# arduino_v2.net
KiCad netlist of a schematic drawn in EAGLE
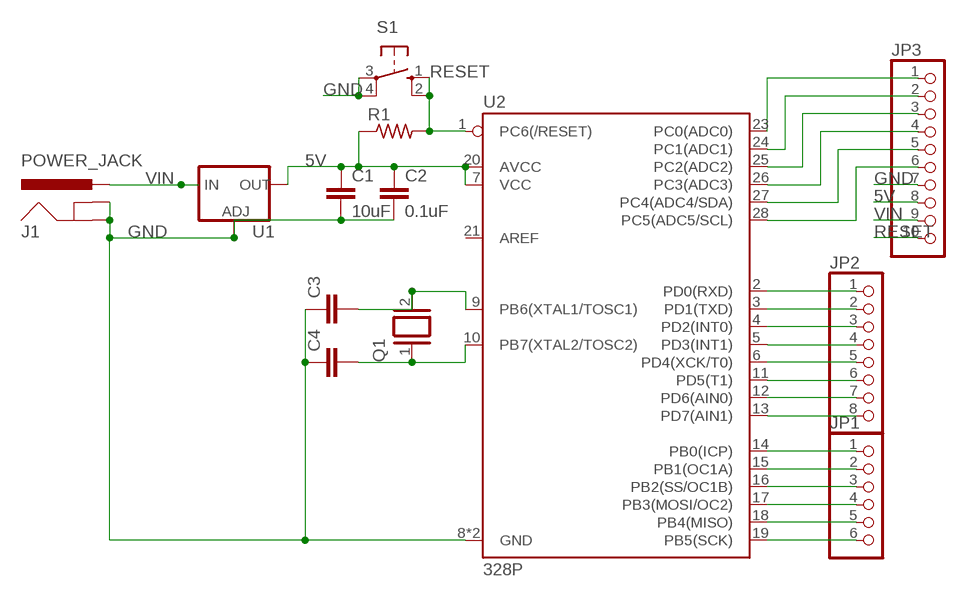
[diagram p0: schematic, sheet 1]

(export (version "E")
  (design (tool "Eeschema 10.0.6"))
  (components
    (comp (ref "C1")
      (value "10uF")
      (footprint "eagle-import:C025-024X044")
      (libsource (lib "eagle-import") (part "C-EU025-024X044"))
    )
    (comp (ref "C2")
      (value "0.1uF")
      (footprint "eagle-import:C025-024X044")
      (libsource (lib "eagle-import") (part "C-EU025-024X044"))
    )
    (comp (ref "C3")
      (value "C-EU025-024X044")
      (footprint "eagle-import:C025-024X044")
      (libsource (lib "eagle-import") (part "C-EU025-024X044"))
    )
    (comp (ref "C4")
      (value "C-EU025-024X044")
      (footprint "eagle-import:C025-024X044")
      (libsource (lib "eagle-import") (part "C-EU025-024X044"))
    )
    (comp (ref "J1")
      (value "POWER_JACK")
      (footprint "eagle-import:POWER_JACK_PTH")
      (libsource (lib "eagle-import") (part "POWER_JACK"))
    )
    (comp (ref "JP1")
      (value "PINHD-1X6")
      (footprint "eagle-import:1X06")
      (libsource (lib "eagle-import") (part "PINHD-1X6"))
    )
    (comp (ref "JP2")
      (value "PINHD-1X8")
      (footprint "eagle-import:1X08")
      (libsource (lib "eagle-import") (part "PINHD-1X8"))
    )
    (comp (ref "JP3")
      (value "PINHD-1X10")
      (footprint "eagle-import:1X10")
      (libsource (lib "eagle-import") (part "PINHD-1X10"))
    )
    (comp (ref "Q1")
      (value "XTAL/S")
      (footprint "eagle-import:QS")
      (libsource (lib "eagle-import") (part "XTAL/S"))
    )
    (comp (ref "R1")
      (value "R-US_0204/7")
      (footprint "eagle-import:0204_7")
      (libsource (lib "eagle-import") (part "R-US_0204/7"))
    )
    (comp (ref "S1")
      (value "10-XX")
      (footprint "eagle-import:B3F-10XX")
      (fields (field (name "MPN") "B3F-1000"))
      (libsource (lib "eagle-import") (part "10-XX"))
    )
    (comp (ref "U1")
      (value "V_REG_LM1117SOT223")
      (footprint "eagle-import:SOT223")
      (libsource (lib "eagle-import") (part "V_REG_LM1117SOT223"))
    )
    (comp (ref "U2")
      (value "328P")
      (footprint "eagle-import:DIP28")
      (libsource (lib "eagle-import") (part "ATMEGA328P_PDIP"))
    )
  )
  (nets
    (net (code "1") (name "/5V") (class "Default")
      (node (ref "C1") (pin "1") (pinfunction "1_1") (pintype "passive"))
      (node (ref "C2") (pin "1") (pinfunction "1_1") (pintype "passive"))
      (node (ref "JP3") (pin "8") (pinfunction "8_8") (pintype "passive"))
      (node (ref "R1") (pin "1") (pinfunction "1_1") (pintype "passive"))
      (node (ref "U1") (pin "2") (pinfunction "OUT_2") (pintype "output"))
      (node (ref "U1") (pin "4") (pinfunction "OUT_4") (pintype "output"))
      (node (ref "U2") (pin "20") (pinfunction "AVCC_20") (pintype "bidirectional"))
      (node (ref "U2") (pin "7") (pinfunction "VCC_7") (pintype "bidirectional"))
    )
    (net (code "2") (name "/GND") (class "Default")
      (node (ref "C1") (pin "2") (pinfunction "2_2") (pintype "passive"))
      (node (ref "C2") (pin "2") (pinfunction "2_2") (pintype "passive"))
      (node (ref "C3") (pin "1") (pinfunction "1_1") (pintype "passive"))
      (node (ref "C4") (pin "1") (pinfunction "1_1") (pintype "passive"))
      (node (ref "J1") (pin "GND") (pinfunction "GND_GND") (pintype "bidirectional"))
      (node (ref "J1") (pin "GNDBREAK") (pinfunction "GNDBREAK_GNDBREAK") (pintype "bidirectional"))
      (node (ref "JP3") (pin "7") (pinfunction "7_7") (pintype "passive"))
      (node (ref "S1") (pin "3") (pinfunction "P_3") (pintype "passive"))
      (node (ref "S1") (pin "4") (pinfunction "P1_4") (pintype "passive"))
      (node (ref "U1") (pin "1") (pinfunction "ADJ_1") (pintype "input"))
      (node (ref "U2") (pin "22") (pinfunction "GND_22") (pintype "bidirectional"))
      (node (ref "U2") (pin "8") (pinfunction "GND_8") (pintype "bidirectional"))
    )
    (net (code "3") (name "/RESET") (class "Default")
      (node (ref "JP3") (pin "10") (pinfunction "10_10") (pintype "passive"))
      (node (ref "R1") (pin "2") (pinfunction "2_2") (pintype "passive"))
      (node (ref "S1") (pin "1") (pinfunction "S_1") (pintype "passive"))
      (node (ref "S1") (pin "2") (pinfunction "S1_2") (pintype "passive"))
      (node (ref "U2") (pin "1") (pinfunction "PC6(/RESET)_1") (pintype "bidirectional"))
    )
    (net (code "4") (name "/VIN") (class "Default")
      (node (ref "J1") (pin "PWR") (pinfunction "PWR_PWR") (pintype "bidirectional"))
      (node (ref "JP3") (pin "9") (pinfunction "9_9") (pintype "passive"))
      (node (ref "U1") (pin "3") (pinfunction "IN_3") (pintype "input"))
    )
    (net (code "5") (name "Net-(U2-PB0(ICP))") (class "Default")
      (node (ref "JP1") (pin "1") (pinfunction "1_1") (pintype "passive"))
      (node (ref "U2") (pin "14") (pinfunction "PB0(ICP)_14") (pintype "bidirectional"))
    )
    (net (code "6") (name "Net-(U2-PB1(OC1A))") (class "Default")
      (node (ref "JP1") (pin "2") (pinfunction "2_2") (pintype "passive"))
      (node (ref "U2") (pin "15") (pinfunction "PB1(OC1A)_15") (pintype "bidirectional"))
    )
    (net (code "7") (name "Net-(U2-PB2(SS{slash}OC1B))") (class "Default")
      (node (ref "JP1") (pin "3") (pinfunction "3_3") (pintype "passive"))
      (node (ref "U2") (pin "16") (pinfunction "PB2(SS/OC1B)_16") (pintype "bidirectional"))
    )
    (net (code "8") (name "Net-(U2-PB3(MOSI{slash}OC2))") (class "Default")
      (node (ref "JP1") (pin "4") (pinfunction "4_4") (pintype "passive"))
      (node (ref "U2") (pin "17") (pinfunction "PB3(MOSI/OC2)_17") (pintype "bidirectional"))
    )
    (net (code "9") (name "Net-(U2-PB4(MISO))") (class "Default")
      (node (ref "JP1") (pin "5") (pinfunction "5_5") (pintype "passive"))
      (node (ref "U2") (pin "18") (pinfunction "PB4(MISO)_18") (pintype "bidirectional"))
    )
    (net (code "10") (name "Net-(U2-PB5(SCK))") (class "Default")
      (node (ref "JP1") (pin "6") (pinfunction "6_6") (pintype "passive"))
      (node (ref "U2") (pin "19") (pinfunction "PB5(SCK)_19") (pintype "bidirectional"))
    )
    (net (code "11") (name "Net-(U2-PB6(XTAL1{slash}TOSC1))") (class "Default")
      (node (ref "C3") (pin "2") (pinfunction "2_2") (pintype "passive"))
      (node (ref "Q1") (pin "2") (pinfunction "2_2") (pintype "passive"))
      (node (ref "U2") (pin "9") (pinfunction "PB6(XTAL1/TOSC1)_9") (pintype "bidirectional"))
    )
    (net (code "12") (name "Net-(U2-PB7(XTAL2{slash}TOSC2))") (class "Default")
      (node (ref "C4") (pin "2") (pinfunction "2_2") (pintype "passive"))
      (node (ref "Q1") (pin "1") (pinfunction "1_1") (pintype "passive"))
      (node (ref "U2") (pin "10") (pinfunction "PB7(XTAL2/TOSC2)_10") (pintype "bidirectional"))
    )
    (net (code "13") (name "Net-(U2-PC0(ADC0))") (class "Default")
      (node (ref "JP3") (pin "1") (pinfunction "1_1") (pintype "passive"))
      (node (ref "U2") (pin "23") (pinfunction "PC0(ADC0)_23") (pintype "bidirectional"))
    )
    (net (code "14") (name "Net-(U2-PC1(ADC1))") (class "Default")
      (node (ref "JP3") (pin "2") (pinfunction "2_2") (pintype "passive"))
      (node (ref "U2") (pin "24") (pinfunction "PC1(ADC1)_24") (pintype "bidirectional"))
    )
    (net (code "15") (name "Net-(U2-PC2(ADC2))") (class "Default")
      (node (ref "JP3") (pin "3") (pinfunction "3_3") (pintype "passive"))
      (node (ref "U2") (pin "25") (pinfunction "PC2(ADC2)_25") (pintype "bidirectional"))
    )
    (net (code "16") (name "Net-(U2-PC3(ADC3))") (class "Default")
      (node (ref "JP3") (pin "4") (pinfunction "4_4") (pintype "passive"))
      (node (ref "U2") (pin "26") (pinfunction "PC3(ADC3)_26") (pintype "bidirectional"))
    )
    (net (code "17") (name "Net-(U2-PC4(ADC4{slash}SDA))") (class "Default")
      (node (ref "JP3") (pin "5") (pinfunction "5_5") (pintype "passive"))
      (node (ref "U2") (pin "27") (pinfunction "PC4(ADC4/SDA)_27") (pintype "bidirectional"))
    )
    (net (code "18") (name "Net-(U2-PC5(ADC5{slash}SCL))") (class "Default")
      (node (ref "JP3") (pin "6") (pinfunction "6_6") (pintype "passive"))
      (node (ref "U2") (pin "28") (pinfunction "PC5(ADC5/SCL)_28") (pintype "bidirectional"))
    )
    (net (code "19") (name "Net-(U2-PD0(RXD))") (class "Default")
      (node (ref "JP2") (pin "1") (pinfunction "1_1") (pintype "passive"))
      (node (ref "U2") (pin "2") (pinfunction "PD0(RXD)_2") (pintype "bidirectional"))
    )
    (net (code "20") (name "Net-(U2-PD1(TXD))") (class "Default")
      (node (ref "JP2") (pin "2") (pinfunction "2_2") (pintype "passive"))
      (node (ref "U2") (pin "3") (pinfunction "PD1(TXD)_3") (pintype "bidirectional"))
    )
    (net (code "21") (name "Net-(U2-PD2(INT0))") (class "Default")
      (node (ref "JP2") (pin "3") (pinfunction "3_3") (pintype "passive"))
      (node (ref "U2") (pin "4") (pinfunction "PD2(INT0)_4") (pintype "bidirectional"))
    )
    (net (code "22") (name "Net-(U2-PD3(INT1))") (class "Default")
      (node (ref "JP2") (pin "4") (pinfunction "4_4") (pintype "passive"))
      (node (ref "U2") (pin "5") (pinfunction "PD3(INT1)_5") (pintype "bidirectional"))
    )
    (net (code "23") (name "Net-(U2-PD4(XCK{slash}T0))") (class "Default")
      (node (ref "JP2") (pin "5") (pinfunction "5_5") (pintype "passive"))
      (node (ref "U2") (pin "6") (pinfunction "PD4(XCK/T0)_6") (pintype "bidirectional"))
    )
    (net (code "24") (name "Net-(U2-PD5(T1))") (class "Default")
      (node (ref "JP2") (pin "6") (pinfunction "6_6") (pintype "passive"))
      (node (ref "U2") (pin "11") (pinfunction "PD5(T1)_11") (pintype "bidirectional"))
    )
    (net (code "25") (name "Net-(U2-PD6(AIN0))") (class "Default")
      (node (ref "JP2") (pin "7") (pinfunction "7_7") (pintype "passive"))
      (node (ref "U2") (pin "12") (pinfunction "PD6(AIN0)_12") (pintype "bidirectional"))
    )
    (net (code "26") (name "Net-(U2-PD7(AIN1))") (class "Default")
      (node (ref "JP2") (pin "8") (pinfunction "8_8") (pintype "passive"))
      (node (ref "U2") (pin "13") (pinfunction "PD7(AIN1)_13") (pintype "bidirectional"))
    )
    (net (code "27") (name "unconnected-(U2-AREF-Pad21)") (class "Default")
      (node (ref "U2") (pin "21") (pinfunction "AREF_21") (pintype "bidirectional"))
    )
  )
)
